# DistribPower_RELAY.net
KiCad netlist of a schematic drawn in Altium Designer
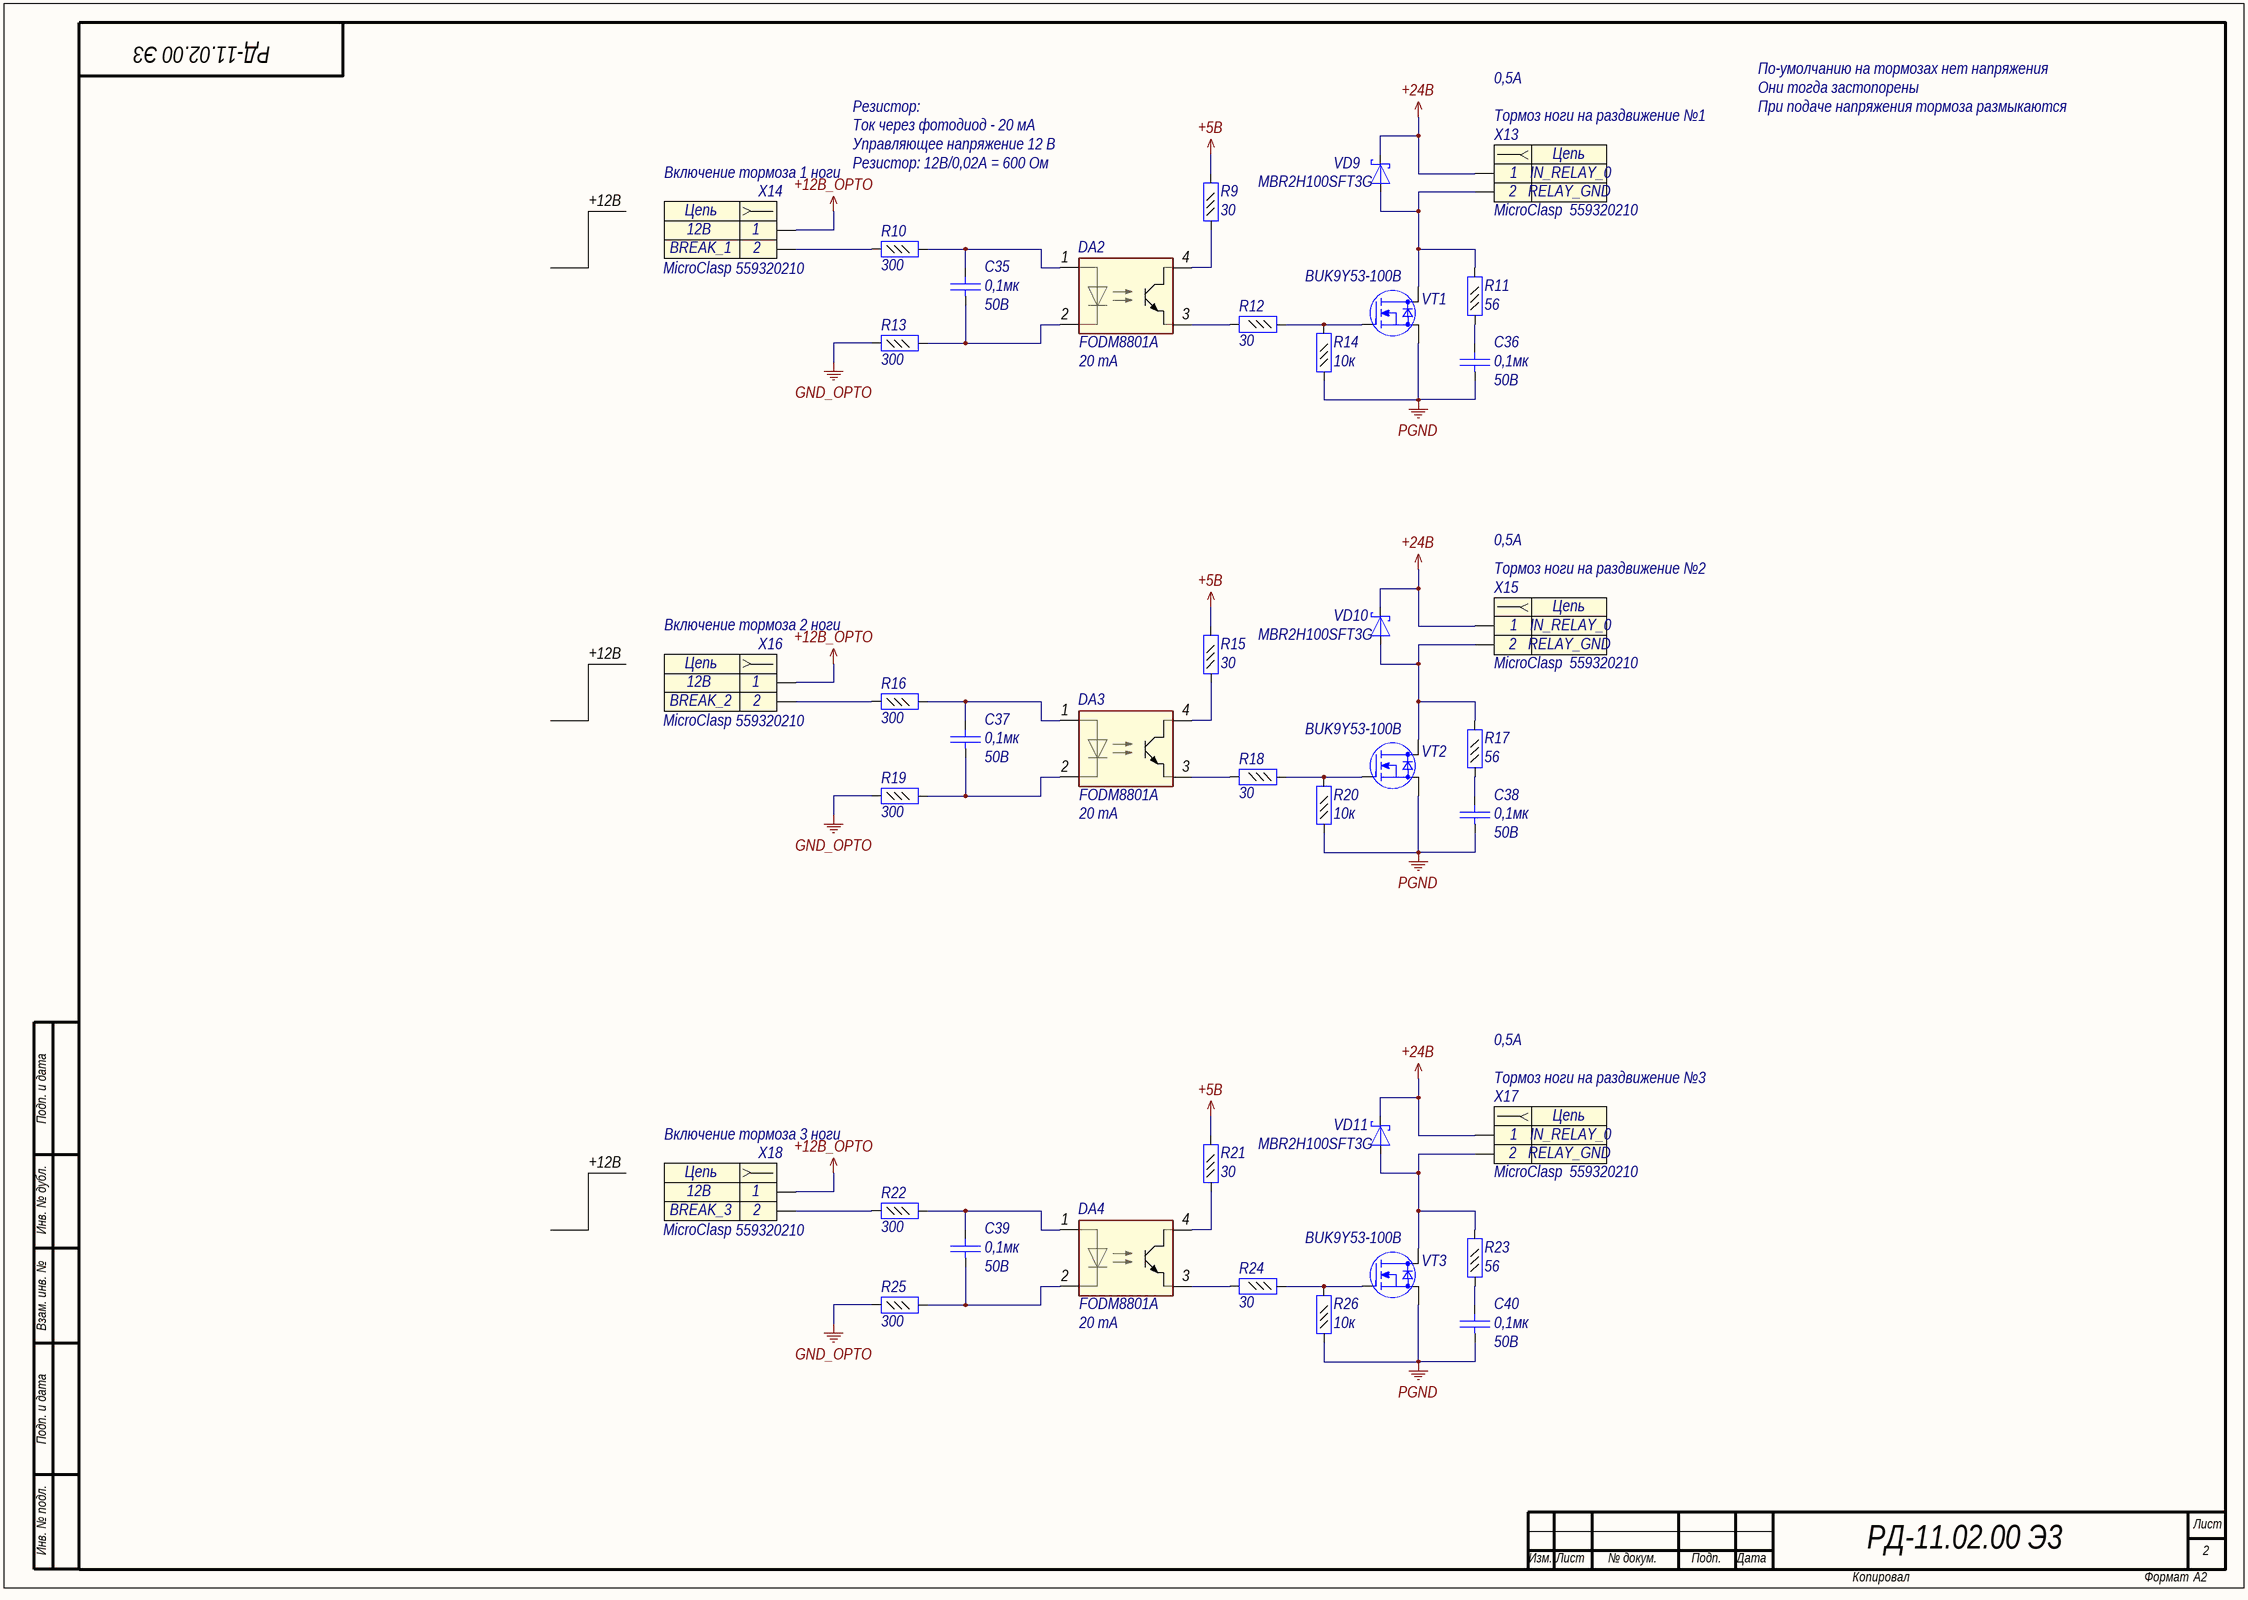
[diagram p0: DistribPower_RELAY.SchDoc]

(export (version "E")
  (design (tool "Eeschema 10.0.6"))
  (components
    (comp (ref "C35")
      (value "0,1мк")
      (footprint "C0402")
      (description "Конденсатор")
      (fields (field (name "VOLTAGE") "50В") (field (name "PART NUMBER") "GRM155R71H104KE14D "))
      (libsource (lib "MOP44") (part "Capacitor"))
    )
    (comp (ref "C36")
      (value "0,1мк")
      (footprint "C0402")
      (description "Конденсатор")
      (fields (field (name "VOLTAGE") "50В") (field (name "PART NUMBER") "GRM155R71H104KE14D "))
      (libsource (lib "MOP44") (part "Capacitor"))
    )
    (comp (ref "C37")
      (value "0,1мк")
      (footprint "C0402")
      (description "Конденсатор")
      (fields (field (name "VOLTAGE") "50В") (field (name "PART NUMBER") "GRM155R71H104KE14D "))
      (libsource (lib "MOP44") (part "Capacitor"))
    )
    (comp (ref "C38")
      (value "0,1мк")
      (footprint "C0402")
      (description "Конденсатор")
      (fields (field (name "VOLTAGE") "50В") (field (name "PART NUMBER") "GRM155R71H104KE14D "))
      (libsource (lib "MOP44") (part "Capacitor"))
    )
    (comp (ref "C39")
      (value "0,1мк")
      (footprint "C0402")
      (description "Конденсатор")
      (fields (field (name "VOLTAGE") "50В") (field (name "PART NUMBER") "GRM155R71H104KE14D "))
      (libsource (lib "MOP44") (part "Capacitor"))
    )
    (comp (ref "C40")
      (value "0,1мк")
      (footprint "C0402")
      (description "Конденсатор")
      (fields (field (name "VOLTAGE") "50В") (field (name "PART NUMBER") "GRM155R71H104KE14D "))
      (libsource (lib "MOP44") (part "Capacitor"))
    )
    (comp (ref "DA2")
      (value "OPTO-1")
      (footprint "Miniflat4")
      (description "Опторазвязка")
      (fields (field (name "PART NUMBER") "FODM8801A") (field (name "MANUFACTURER") "ON Semiconductor"))
      (libsource (lib "MOP44") (part "OPTO-1"))
    )
    (comp (ref "DA3")
      (value "OPTO-1")
      (footprint "Miniflat4")
      (description "Опторазвязка")
      (fields (field (name "PART NUMBER") "FODM8801A") (field (name "MANUFACTURER") "ON Semiconductor"))
      (libsource (lib "MOP44") (part "OPTO-1"))
    )
    (comp (ref "DA4")
      (value "OPTO-1")
      (footprint "Miniflat4")
      (description "Опторазвязка")
      (fields (field (name "PART NUMBER") "FODM8801A") (field (name "MANUFACTURER") "ON Semiconductor"))
      (libsource (lib "MOP44") (part "OPTO-1"))
    )
    (comp (ref "R9")
      (value "30")
      (footprint "R0402")
      (description "Резистор")
      (fields (field (name "PART NUMBER") "RC0402FR-0730RL") (field (name "POWER") "0,062Вт"))
      (libsource (lib "") (part "Resistor_0,062Вт_1"))
    )
    (comp (ref "R10")
      (value "300")
      (footprint "R0402")
      (description "Резистор")
      (fields (field (name "PART NUMBER") "RC0402FR-07300RL") (field (name "POWER") "0,062Вт"))
      (libsource (lib "MOP44") (part "Resistor_0,062Вт"))
    )
    (comp (ref "R11")
      (value "56")
      (footprint "R0402")
      (description "Резистор")
      (fields (field (name "PART NUMBER") "RC0402FR-0756RL") (field (name "POWER") "0,062Вт"))
      (libsource (lib "") (part "Resistor_0,062Вт_1"))
    )
    (comp (ref "R12")
      (value "30")
      (footprint "R0402")
      (description "Резистор")
      (fields (field (name "PART NUMBER") "RC0402FR-0730RL") (field (name "POWER") "0,062Вт"))
      (libsource (lib "") (part "Resistor_0,062Вт_2"))
    )
    (comp (ref "R13")
      (value "300")
      (footprint "R0402")
      (description "Резистор")
      (fields (field (name "PART NUMBER") "RC0402FR-07300RL") (field (name "POWER") "0,062Вт"))
      (libsource (lib "MOP44") (part "Resistor_0,062Вт"))
    )
    (comp (ref "R14")
      (value "10к")
      (footprint "R0402")
      (description "Резистор")
      (fields (field (name "PART NUMBER") "RC0402FR-0710KL") (field (name "POWER") "0,062Вт"))
      (libsource (lib "") (part "Resistor_0,062Вт_1"))
    )
    (comp (ref "R15")
      (value "30")
      (footprint "R0402")
      (description "Резистор")
      (fields (field (name "PART NUMBER") "RC0402FR-0730RL") (field (name "POWER") "0,062Вт"))
      (libsource (lib "") (part "Resistor_0,062Вт_1"))
    )
    (comp (ref "R16")
      (value "300")
      (footprint "R0402")
      (description "Резистор")
      (fields (field (name "PART NUMBER") "RC0402FR-07300RL") (field (name "POWER") "0,062Вт"))
      (libsource (lib "MOP44") (part "Resistor_0,062Вт"))
    )
    (comp (ref "R17")
      (value "56")
      (footprint "R0402")
      (description "Резистор")
      (fields (field (name "PART NUMBER") "RC0402FR-0756RL") (field (name "POWER") "0,062Вт"))
      (libsource (lib "") (part "Resistor_0,062Вт_1"))
    )
    (comp (ref "R18")
      (value "30")
      (footprint "R0402")
      (description "Резистор")
      (fields (field (name "PART NUMBER") "RC0402FR-0730RL") (field (name "POWER") "0,062Вт"))
      (libsource (lib "") (part "Resistor_0,062Вт_2"))
    )
    (comp (ref "R19")
      (value "300")
      (footprint "R0402")
      (description "Резистор")
      (fields (field (name "PART NUMBER") "RC0402FR-07300RL") (field (name "POWER") "0,062Вт"))
      (libsource (lib "MOP44") (part "Resistor_0,062Вт"))
    )
    (comp (ref "R20")
      (value "10к")
      (footprint "R0402")
      (description "Резистор")
      (fields (field (name "PART NUMBER") "RC0402FR-0710KL") (field (name "POWER") "0,062Вт"))
      (libsource (lib "") (part "Resistor_0,062Вт_1"))
    )
    (comp (ref "R21")
      (value "30")
      (footprint "R0402")
      (description "Резистор")
      (fields (field (name "PART NUMBER") "RC0402FR-0730RL") (field (name "POWER") "0,062Вт"))
      (libsource (lib "") (part "Resistor_0,062Вт_1"))
    )
    (comp (ref "R22")
      (value "300")
      (footprint "R0402")
      (description "Резистор")
      (fields (field (name "PART NUMBER") "RC0402FR-07300RL") (field (name "POWER") "0,062Вт"))
      (libsource (lib "MOP44") (part "Resistor_0,062Вт"))
    )
    (comp (ref "R23")
      (value "56")
      (footprint "R0402")
      (description "Резистор")
      (fields (field (name "PART NUMBER") "RC0402FR-0756RL") (field (name "POWER") "0,062Вт"))
      (libsource (lib "") (part "Resistor_0,062Вт_1"))
    )
    (comp (ref "R24")
      (value "30")
      (footprint "R0402")
      (description "Резистор")
      (fields (field (name "PART NUMBER") "RC0402FR-0730RL") (field (name "POWER") "0,062Вт"))
      (libsource (lib "") (part "Resistor_0,062Вт_2"))
    )
    (comp (ref "R25")
      (value "300")
      (footprint "R0402")
      (description "Резистор")
      (fields (field (name "PART NUMBER") "RC0402FR-07300RL") (field (name "POWER") "0,062Вт"))
      (libsource (lib "MOP44") (part "Resistor_0,062Вт"))
    )
    (comp (ref "R26")
      (value "10к")
      (footprint "R0402")
      (description "Резистор")
      (fields (field (name "PART NUMBER") "RC0402FR-0710KL") (field (name "POWER") "0,062Вт"))
      (libsource (lib "") (part "Resistor_0,062Вт_1"))
    )
    (comp (ref "VD9")
      (value "DiodeSchottky")
      (footprint "SOD-123")
      (description "Диод Шоттки")
      (fields (field (name "PART NUMBER") "MBR2H100SFT3G"))
      (libsource (lib "MOP44") (part "DiodeSchottky"))
    )
    (comp (ref "VD10")
      (value "DiodeSchottky")
      (footprint "SOD-123")
      (description "Диод Шоттки")
      (fields (field (name "PART NUMBER") "MBR2H100SFT3G"))
      (libsource (lib "MOP44") (part "DiodeSchottky"))
    )
    (comp (ref "VD11")
      (value "DiodeSchottky")
      (footprint "SOD-123")
      (description "Диод Шоттки")
      (fields (field (name "PART NUMBER") "MBR2H100SFT3G"))
      (libsource (lib "MOP44") (part "DiodeSchottky"))
    )
    (comp (ref "VT1")
      (value "N-MOSFET")
      (footprint "SOT669")
      (fields (field (name "PART NUMBER") "BUK9Y53-100B") (field (name "MANUFACTURER") "Nexperia"))
      (libsource (lib "MOP44") (part "N-MOSFET"))
    )
    (comp (ref "VT2")
      (value "N-MOSFET")
      (footprint "SOT669")
      (fields (field (name "PART NUMBER") "BUK9Y53-100B") (field (name "MANUFACTURER") "Nexperia"))
      (libsource (lib "MOP44") (part "N-MOSFET"))
    )
    (comp (ref "VT3")
      (value "N-MOSFET")
      (footprint "SOT669")
      (fields (field (name "PART NUMBER") "BUK9Y53-100B") (field (name "MANUFACTURER") "Nexperia"))
      (libsource (lib "MOP44") (part "N-MOSFET"))
    )
    (comp (ref "X13")
      (value "Тормоз ноги на раздвижение №1")
      (footprint "MOLEX_559320210")
      (description "Разъем - 2 конт. розетка")
      (fields (field (name "PART NAME") "MicroClasp") (field (name "PART NUMBER") "559320210"))
      (libsource (lib "") (part "Header_2_sct_1"))
    )
    (comp (ref "X14")
      (value "Включение тормоза 1 ноги")
      (footprint "MOLEX_559320210")
      (description "Разъем - 2 конт. розетка")
      (fields (field (name "PART NAME") "MicroClasp") (field (name "PART NUMBER") "559320210"))
      (libsource (lib "MOP44") (part "Header_2_sct"))
    )
    (comp (ref "X15")
      (value "Тормоз ноги на раздвижение №2")
      (footprint "MOLEX_559320210")
      (description "Разъем - 2 конт. розетка")
      (fields (field (name "PART NAME") "MicroClasp") (field (name "PART NUMBER") "559320210"))
      (libsource (lib "") (part "Header_2_sct_1"))
    )
    (comp (ref "X16")
      (value "Включение тормоза 2 ноги")
      (footprint "MOLEX_559320210")
      (description "Разъем - 2 конт. розетка")
      (fields (field (name "PART NAME") "MicroClasp") (field (name "PART NUMBER") "559320210"))
      (libsource (lib "MOP44") (part "Header_2_sct"))
    )
    (comp (ref "X17")
      (value "Тормоз ноги на раздвижение №3")
      (footprint "MOLEX_559320210")
      (description "Разъем - 2 конт. розетка")
      (fields (field (name "PART NAME") "MicroClasp") (field (name "PART NUMBER") "559320210"))
      (libsource (lib "") (part "Header_2_sct_1"))
    )
    (comp (ref "X18")
      (value "Включение тормоза 3 ноги")
      (footprint "MOLEX_559320210")
      (description "Разъем - 2 конт. розетка")
      (fields (field (name "PART NAME") "MicroClasp") (field (name "PART NUMBER") "559320210"))
      (libsource (lib "MOP44") (part "Header_2_sct"))
    )
  )
  (nets
    (net (code "1") (name "+5B") (class "Default")
      (node (ref "R15") (pin "2") (pinfunction "2_2") (pintype "passive"))
      (node (ref "R21") (pin "2") (pinfunction "2_2") (pintype "passive"))
      (node (ref "R9") (pin "2") (pinfunction "2_2") (pintype "passive"))
    )
    (net (code "2") (name "+12B_OPTO") (class "Default")
      (node (ref "X14") (pin "1") (pinfunction "1_1") (pintype "passive"))
      (node (ref "X16") (pin "1") (pinfunction "1_1") (pintype "passive"))
      (node (ref "X18") (pin "1") (pinfunction "1_1") (pintype "passive"))
    )
    (net (code "3") (name "+24B") (class "Default")
      (node (ref "VD10") (pin "1") (pinfunction "K_1") (pintype "passive"))
      (node (ref "VD11") (pin "1") (pinfunction "K_1") (pintype "passive"))
      (node (ref "VD9") (pin "1") (pinfunction "K_1") (pintype "passive"))
      (node (ref "X13") (pin "1") (pinfunction "1_1") (pintype "passive"))
      (node (ref "X15") (pin "1") (pinfunction "1_1") (pintype "passive"))
      (node (ref "X17") (pin "1") (pinfunction "1_1") (pintype "passive"))
    )
    (net (code "4") (name "GND_OPTO") (class "Default")
      (node (ref "R13") (pin "1") (pinfunction "1_1") (pintype "passive"))
      (node (ref "R19") (pin "1") (pinfunction "1_1") (pintype "passive"))
      (node (ref "R25") (pin "1") (pinfunction "1_1") (pintype "passive"))
    )
    (net (code "5") (name "Net-(C35-Pad1)") (class "Default")
      (node (ref "C35") (pin "1") (pinfunction "1_1") (pintype "passive"))
      (node (ref "DA2") (pin "2") (pintype "passive"))
      (node (ref "R13") (pin "2") (pinfunction "2_2") (pintype "passive"))
    )
    (net (code "6") (name "Net-(C35-Pad2)") (class "Default")
      (node (ref "C35") (pin "2") (pinfunction "2_2") (pintype "passive"))
      (node (ref "DA2") (pin "1") (pintype "passive"))
      (node (ref "R10") (pin "2") (pinfunction "2_2") (pintype "passive"))
    )
    (net (code "7") (name "Net-(C36-Pad2)") (class "Default")
      (node (ref "C36") (pin "2") (pinfunction "2_2") (pintype "passive"))
      (node (ref "R11") (pin "1") (pinfunction "1_1") (pintype "passive"))
    )
    (net (code "8") (name "Net-(C37-Pad1)") (class "Default")
      (node (ref "C37") (pin "1") (pinfunction "1_1") (pintype "passive"))
      (node (ref "DA3") (pin "2") (pintype "passive"))
      (node (ref "R19") (pin "2") (pinfunction "2_2") (pintype "passive"))
    )
    (net (code "9") (name "Net-(C37-Pad2)") (class "Default")
      (node (ref "C37") (pin "2") (pinfunction "2_2") (pintype "passive"))
      (node (ref "DA3") (pin "1") (pintype "passive"))
      (node (ref "R16") (pin "2") (pinfunction "2_2") (pintype "passive"))
    )
    (net (code "10") (name "Net-(C38-Pad2)") (class "Default")
      (node (ref "C38") (pin "2") (pinfunction "2_2") (pintype "passive"))
      (node (ref "R17") (pin "1") (pinfunction "1_1") (pintype "passive"))
    )
    (net (code "11") (name "Net-(C39-Pad1)") (class "Default")
      (node (ref "C39") (pin "1") (pinfunction "1_1") (pintype "passive"))
      (node (ref "DA4") (pin "2") (pintype "passive"))
      (node (ref "R25") (pin "2") (pinfunction "2_2") (pintype "passive"))
    )
    (net (code "12") (name "Net-(C39-Pad2)") (class "Default")
      (node (ref "C39") (pin "2") (pinfunction "2_2") (pintype "passive"))
      (node (ref "DA4") (pin "1") (pintype "passive"))
      (node (ref "R22") (pin "2") (pinfunction "2_2") (pintype "passive"))
    )
    (net (code "13") (name "Net-(C40-Pad2)") (class "Default")
      (node (ref "C40") (pin "2") (pinfunction "2_2") (pintype "passive"))
      (node (ref "R23") (pin "1") (pinfunction "1_1") (pintype "passive"))
    )
    (net (code "14") (name "Net-(DA2-Pad3)") (class "Default")
      (node (ref "DA2") (pin "3") (pintype "passive"))
      (node (ref "R12") (pin "2") (pinfunction "2_2") (pintype "passive"))
    )
    (net (code "15") (name "Net-(DA2-Pad4)") (class "Default")
      (node (ref "DA2") (pin "4") (pintype "passive"))
      (node (ref "R9") (pin "1") (pinfunction "1_1") (pintype "passive"))
    )
    (net (code "16") (name "Net-(DA3-Pad3)") (class "Default")
      (node (ref "DA3") (pin "3") (pintype "passive"))
      (node (ref "R18") (pin "2") (pinfunction "2_2") (pintype "passive"))
    )
    (net (code "17") (name "Net-(DA3-Pad4)") (class "Default")
      (node (ref "DA3") (pin "4") (pintype "passive"))
      (node (ref "R15") (pin "1") (pinfunction "1_1") (pintype "passive"))
    )
    (net (code "18") (name "Net-(DA4-Pad3)") (class "Default")
      (node (ref "DA4") (pin "3") (pintype "passive"))
      (node (ref "R24") (pin "2") (pinfunction "2_2") (pintype "passive"))
    )
    (net (code "19") (name "Net-(DA4-Pad4)") (class "Default")
      (node (ref "DA4") (pin "4") (pintype "passive"))
      (node (ref "R21") (pin "1") (pinfunction "1_1") (pintype "passive"))
    )
    (net (code "20") (name "Net-(R10-Pad1)") (class "Default")
      (node (ref "R10") (pin "1") (pinfunction "1_1") (pintype "passive"))
      (node (ref "X14") (pin "2") (pinfunction "2_2") (pintype "passive"))
    )
    (net (code "21") (name "Net-(R16-Pad1)") (class "Default")
      (node (ref "R16") (pin "1") (pinfunction "1_1") (pintype "passive"))
      (node (ref "X16") (pin "2") (pinfunction "2_2") (pintype "passive"))
    )
    (net (code "22") (name "Net-(R22-Pad1)") (class "Default")
      (node (ref "R22") (pin "1") (pinfunction "1_1") (pintype "passive"))
      (node (ref "X18") (pin "2") (pinfunction "2_2") (pintype "passive"))
    )
    (net (code "23") (name "Net-(VD9-A)") (class "Default")
      (node (ref "R11") (pin "2") (pinfunction "2_2") (pintype "passive"))
      (node (ref "VD9") (pin "2") (pinfunction "A_2") (pintype "passive"))
      (node (ref "VT1") (pin "2") (pinfunction "D_2") (pintype "passive"))
      (node (ref "X13") (pin "2") (pinfunction "2_2") (pintype "passive"))
    )
    (net (code "24") (name "Net-(VD10-A)") (class "Default")
      (node (ref "R17") (pin "2") (pinfunction "2_2") (pintype "passive"))
      (node (ref "VD10") (pin "2") (pinfunction "A_2") (pintype "passive"))
      (node (ref "VT2") (pin "2") (pinfunction "D_2") (pintype "passive"))
      (node (ref "X15") (pin "2") (pinfunction "2_2") (pintype "passive"))
    )
    (net (code "25") (name "Net-(VD11-A)") (class "Default")
      (node (ref "R23") (pin "2") (pinfunction "2_2") (pintype "passive"))
      (node (ref "VD11") (pin "2") (pinfunction "A_2") (pintype "passive"))
      (node (ref "VT3") (pin "2") (pinfunction "D_2") (pintype "passive"))
      (node (ref "X17") (pin "2") (pinfunction "2_2") (pintype "passive"))
    )
    (net (code "26") (name "Net-(VT1-G)") (class "Default")
      (node (ref "R12") (pin "1") (pinfunction "1_1") (pintype "passive"))
      (node (ref "R14") (pin "2") (pinfunction "2_2") (pintype "passive"))
      (node (ref "VT1") (pin "1") (pinfunction "G_1") (pintype "passive"))
    )
    (net (code "27") (name "Net-(VT2-G)") (class "Default")
      (node (ref "R18") (pin "1") (pinfunction "1_1") (pintype "passive"))
      (node (ref "R20") (pin "2") (pinfunction "2_2") (pintype "passive"))
      (node (ref "VT2") (pin "1") (pinfunction "G_1") (pintype "passive"))
    )
    (net (code "28") (name "Net-(VT3-G)") (class "Default")
      (node (ref "R24") (pin "1") (pinfunction "1_1") (pintype "passive"))
      (node (ref "R26") (pin "2") (pinfunction "2_2") (pintype "passive"))
      (node (ref "VT3") (pin "1") (pinfunction "G_1") (pintype "passive"))
    )
    (net (code "29") (name "PGND") (class "Default")
      (node (ref "C36") (pin "1") (pinfunction "1_1") (pintype "passive"))
      (node (ref "C38") (pin "1") (pinfunction "1_1") (pintype "passive"))
      (node (ref "C40") (pin "1") (pinfunction "1_1") (pintype "passive"))
      (node (ref "R14") (pin "1") (pinfunction "1_1") (pintype "passive"))
      (node (ref "R20") (pin "1") (pinfunction "1_1") (pintype "passive"))
      (node (ref "R26") (pin "1") (pinfunction "1_1") (pintype "passive"))
      (node (ref "VT1") (pin "3") (pinfunction "S_3") (pintype "passive"))
      (node (ref "VT2") (pin "3") (pinfunction "S_3") (pintype "passive"))
      (node (ref "VT3") (pin "3") (pinfunction "S_3") (pintype "passive"))
    )
  )
)
